# RS9110-N-11-22_Breakout.net
KiCad netlist of a schematic drawn in EAGLE
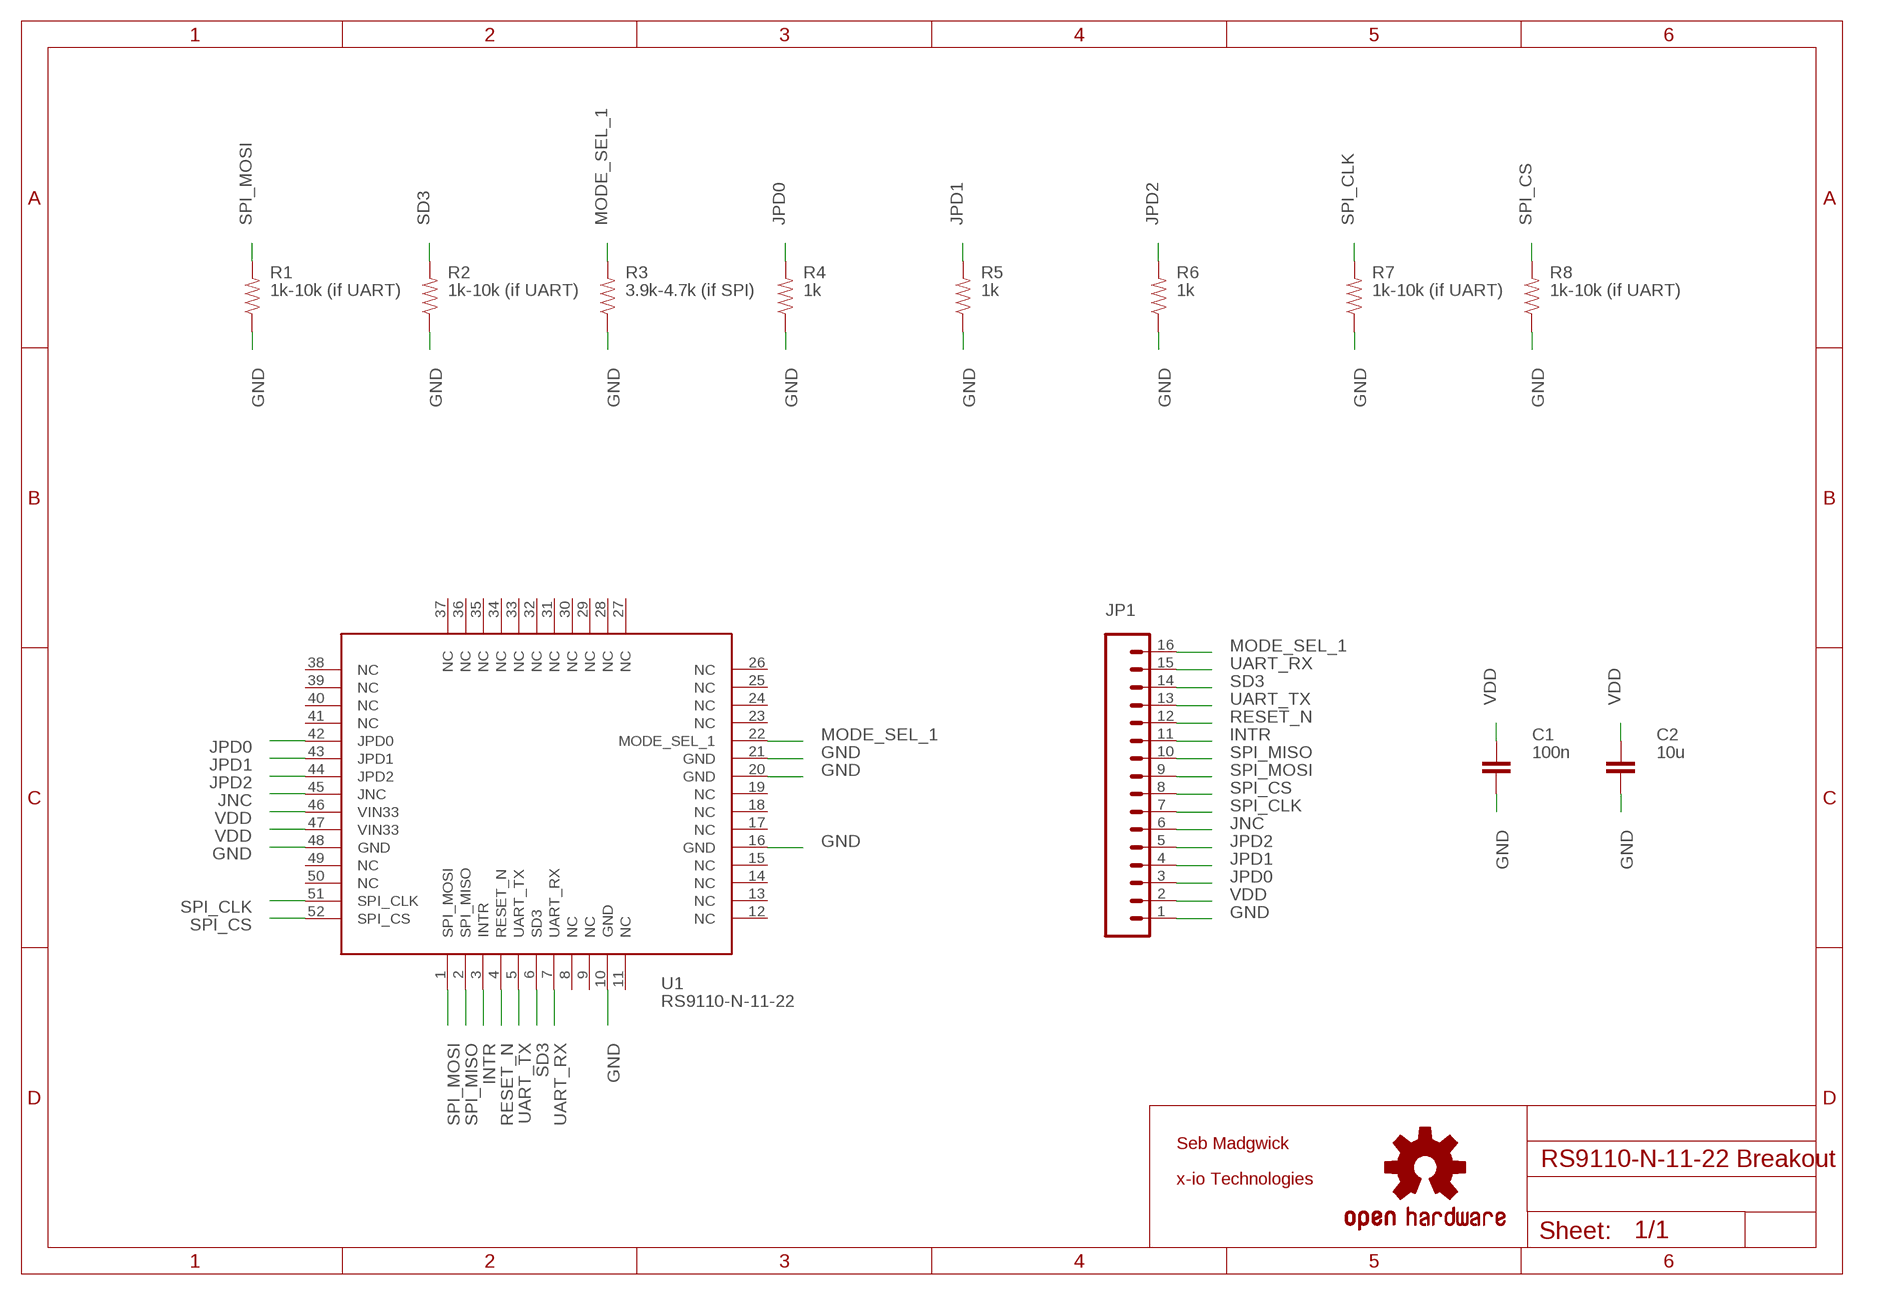
[diagram p0: schematic, sheet 1]

(export (version "E")
  (design (tool "Eeschema 10.0.6"))
  (components
    (comp (ref "C1")
      (value "100n")
      (footprint "eagle-import:0603-CAP")
      (libsource (lib "eagle-import") (part "CAP0603-CAP"))
    )
    (comp (ref "C2")
      (value "10u")
      (footprint "eagle-import:0603-CAP")
      (libsource (lib "eagle-import") (part "CAP0603-CAP"))
    )
    (comp (ref "JP1")
      (value "M16PTH")
      (footprint "eagle-import:1X16")
      (libsource (lib "eagle-import") (part "M16PTH"))
    )
    (comp (ref "LOGO1")
      (value "OSHW-LOGOS")
      (footprint "eagle-import:OSHW-LOGO-S")
      (libsource (lib "eagle-import") (part "OSHW-LOGOS"))
    )
    (comp (ref "R1")
      (value "1k-10k (if UART)")
      (footprint "eagle-import:0603-RES")
      (libsource (lib "eagle-import") (part "RESISTOR0603"))
    )
    (comp (ref "R2")
      (value "1k-10k (if UART)")
      (footprint "eagle-import:0603-RES")
      (libsource (lib "eagle-import") (part "RESISTOR0603"))
    )
    (comp (ref "R3")
      (value "3.9k-4.7k (if SPI)")
      (footprint "eagle-import:0603-RES")
      (libsource (lib "eagle-import") (part "RESISTOR0603"))
    )
    (comp (ref "R4")
      (value "1k")
      (footprint "eagle-import:0603-RES")
      (libsource (lib "eagle-import") (part "RESISTOR0603"))
    )
    (comp (ref "R5")
      (value "1k")
      (footprint "eagle-import:0603-RES")
      (libsource (lib "eagle-import") (part "RESISTOR0603"))
    )
    (comp (ref "R6")
      (value "1k")
      (footprint "eagle-import:0603-RES")
      (libsource (lib "eagle-import") (part "RESISTOR0603"))
    )
    (comp (ref "R7")
      (value "1k-10k (if UART)")
      (footprint "eagle-import:0603-RES")
      (libsource (lib "eagle-import") (part "RESISTOR0603"))
    )
    (comp (ref "R8")
      (value "1k-10k (if UART)")
      (footprint "eagle-import:0603-RES")
      (libsource (lib "eagle-import") (part "RESISTOR0603"))
    )
    (comp (ref "U1")
      (value "RS9110-N-11-22")
      (footprint "eagle-import:RS9110-N-11-22")
      (libsource (lib "eagle-import") (part "RS9110-N-11-22"))
    )
  )
  (nets
    (net (code "1") (name "/GND") (class "Default")
      (node (ref "C1") (pin "2") (pinfunction "2_2") (pintype "passive"))
      (node (ref "C2") (pin "2") (pinfunction "2_2") (pintype "passive"))
      (node (ref "JP1") (pin "1") (pinfunction "1_1") (pintype "passive"))
      (node (ref "R1") (pin "1") (pinfunction "1_1") (pintype "passive"))
      (node (ref "R2") (pin "1") (pinfunction "1_1") (pintype "passive"))
      (node (ref "R3") (pin "1") (pinfunction "1_1") (pintype "passive"))
      (node (ref "R4") (pin "1") (pinfunction "1_1") (pintype "passive"))
      (node (ref "R5") (pin "1") (pinfunction "1_1") (pintype "passive"))
      (node (ref "R6") (pin "1") (pinfunction "1_1") (pintype "passive"))
      (node (ref "R7") (pin "1") (pinfunction "1_1") (pintype "passive"))
      (node (ref "R8") (pin "1") (pinfunction "1_1") (pintype "passive"))
      (node (ref "U1") (pin "10") (pinfunction "GND_10") (pintype "bidirectional"))
      (node (ref "U1") (pin "16") (pinfunction "GND_16") (pintype "bidirectional"))
      (node (ref "U1") (pin "20") (pinfunction "GND_20") (pintype "bidirectional"))
      (node (ref "U1") (pin "21") (pinfunction "GND_21") (pintype "bidirectional"))
      (node (ref "U1") (pin "48") (pinfunction "GND_48") (pintype "bidirectional"))
    )
    (net (code "2") (name "/INTR") (class "Default")
      (node (ref "JP1") (pin "11") (pinfunction "11_11") (pintype "passive"))
      (node (ref "U1") (pin "3") (pinfunction "INTR_3") (pintype "bidirectional"))
    )
    (net (code "3") (name "/JNC") (class "Default")
      (node (ref "JP1") (pin "6") (pinfunction "6_6") (pintype "passive"))
      (node (ref "U1") (pin "45") (pinfunction "JNC_45") (pintype "bidirectional"))
    )
    (net (code "4") (name "/JPD0") (class "Default")
      (node (ref "JP1") (pin "3") (pinfunction "3_3") (pintype "passive"))
      (node (ref "R4") (pin "2") (pinfunction "2_2") (pintype "passive"))
      (node (ref "U1") (pin "42") (pinfunction "JPD0_42") (pintype "bidirectional"))
    )
    (net (code "5") (name "/JPD1") (class "Default")
      (node (ref "JP1") (pin "4") (pinfunction "4_4") (pintype "passive"))
      (node (ref "R5") (pin "2") (pinfunction "2_2") (pintype "passive"))
      (node (ref "U1") (pin "43") (pinfunction "JPD1_43") (pintype "bidirectional"))
    )
    (net (code "6") (name "/JPD2") (class "Default")
      (node (ref "JP1") (pin "5") (pinfunction "5_5") (pintype "passive"))
      (node (ref "R6") (pin "2") (pinfunction "2_2") (pintype "passive"))
      (node (ref "U1") (pin "44") (pinfunction "JPD2_44") (pintype "bidirectional"))
    )
    (net (code "7") (name "/MODE_SEL_1") (class "Default")
      (node (ref "JP1") (pin "16") (pinfunction "16_16") (pintype "passive"))
      (node (ref "R3") (pin "2") (pinfunction "2_2") (pintype "passive"))
      (node (ref "U1") (pin "22") (pinfunction "MODE_SEL_1_22") (pintype "bidirectional"))
    )
    (net (code "8") (name "/RESET_N") (class "Default")
      (node (ref "JP1") (pin "12") (pinfunction "12_12") (pintype "passive"))
      (node (ref "U1") (pin "4") (pinfunction "RESET_N_4") (pintype "bidirectional"))
    )
    (net (code "9") (name "/SD3") (class "Default")
      (node (ref "JP1") (pin "14") (pinfunction "14_14") (pintype "passive"))
      (node (ref "R2") (pin "2") (pinfunction "2_2") (pintype "passive"))
      (node (ref "U1") (pin "6") (pinfunction "SD3_6") (pintype "bidirectional"))
    )
    (net (code "10") (name "/SPI_CLK") (class "Default")
      (node (ref "JP1") (pin "7") (pinfunction "7_7") (pintype "passive"))
      (node (ref "R7") (pin "2") (pinfunction "2_2") (pintype "passive"))
      (node (ref "U1") (pin "51") (pinfunction "SPI_CLK_51") (pintype "bidirectional"))
    )
    (net (code "11") (name "/SPI_CS") (class "Default")
      (node (ref "JP1") (pin "8") (pinfunction "8_8") (pintype "passive"))
      (node (ref "R8") (pin "2") (pinfunction "2_2") (pintype "passive"))
      (node (ref "U1") (pin "52") (pinfunction "SPI_CS_52") (pintype "bidirectional"))
    )
    (net (code "12") (name "/SPI_MISO") (class "Default")
      (node (ref "JP1") (pin "10") (pinfunction "10_10") (pintype "passive"))
      (node (ref "U1") (pin "2") (pinfunction "SPI_MISO_2") (pintype "bidirectional"))
    )
    (net (code "13") (name "/SPI_MOSI") (class "Default")
      (node (ref "JP1") (pin "9") (pinfunction "9_9") (pintype "passive"))
      (node (ref "R1") (pin "2") (pinfunction "2_2") (pintype "passive"))
      (node (ref "U1") (pin "1") (pinfunction "SPI_MOSI_1") (pintype "bidirectional"))
    )
    (net (code "14") (name "/UART_RX") (class "Default")
      (node (ref "JP1") (pin "15") (pinfunction "15_15") (pintype "passive"))
      (node (ref "U1") (pin "7") (pinfunction "UART_RX_7") (pintype "bidirectional"))
    )
    (net (code "15") (name "/UART_TX") (class "Default")
      (node (ref "JP1") (pin "13") (pinfunction "13_13") (pintype "passive"))
      (node (ref "U1") (pin "5") (pinfunction "UART_TX_5") (pintype "bidirectional"))
    )
    (net (code "16") (name "/VDD") (class "Default")
      (node (ref "C1") (pin "1") (pinfunction "1_1") (pintype "passive"))
      (node (ref "C2") (pin "1") (pinfunction "1_1") (pintype "passive"))
      (node (ref "JP1") (pin "2") (pinfunction "2_2") (pintype "passive"))
      (node (ref "U1") (pin "46") (pinfunction "VIN33_46") (pintype "bidirectional"))
      (node (ref "U1") (pin "47") (pinfunction "VIN33_47") (pintype "bidirectional"))
    )
    (net (code "17") (name "unconnected-(U1-NC-Pad8)") (class "Default")
      (node (ref "U1") (pin "8") (pinfunction "NC_8") (pintype "bidirectional"))
    )
    (net (code "18") (name "unconnected-(U1-NC-Pad9)") (class "Default")
      (node (ref "U1") (pin "9") (pinfunction "NC_9") (pintype "bidirectional"))
    )
    (net (code "19") (name "unconnected-(U1-NC-Pad11)") (class "Default")
      (node (ref "U1") (pin "11") (pinfunction "NC_11") (pintype "bidirectional"))
    )
    (net (code "20") (name "unconnected-(U1-NC-Pad12)") (class "Default")
      (node (ref "U1") (pin "12") (pinfunction "NC_12") (pintype "bidirectional"))
    )
    (net (code "21") (name "unconnected-(U1-NC-Pad13)") (class "Default")
      (node (ref "U1") (pin "13") (pinfunction "NC_13") (pintype "bidirectional"))
    )
    (net (code "22") (name "unconnected-(U1-NC-Pad14)") (class "Default")
      (node (ref "U1") (pin "14") (pinfunction "NC_14") (pintype "bidirectional"))
    )
    (net (code "23") (name "unconnected-(U1-NC-Pad15)") (class "Default")
      (node (ref "U1") (pin "15") (pinfunction "NC_15") (pintype "bidirectional"))
    )
    (net (code "24") (name "unconnected-(U1-NC-Pad17)") (class "Default")
      (node (ref "U1") (pin "17") (pinfunction "NC_17") (pintype "bidirectional"))
    )
    (net (code "25") (name "unconnected-(U1-NC-Pad18)") (class "Default")
      (node (ref "U1") (pin "18") (pinfunction "NC_18") (pintype "bidirectional"))
    )
    (net (code "26") (name "unconnected-(U1-NC-Pad19)") (class "Default")
      (node (ref "U1") (pin "19") (pinfunction "NC_19") (pintype "bidirectional"))
    )
    (net (code "27") (name "unconnected-(U1-NC-Pad23)") (class "Default")
      (node (ref "U1") (pin "23") (pinfunction "NC_23") (pintype "bidirectional"))
    )
    (net (code "28") (name "unconnected-(U1-NC-Pad24)") (class "Default")
      (node (ref "U1") (pin "24") (pinfunction "NC_24") (pintype "bidirectional"))
    )
    (net (code "29") (name "unconnected-(U1-NC-Pad25)") (class "Default")
      (node (ref "U1") (pin "25") (pinfunction "NC_25") (pintype "bidirectional"))
    )
    (net (code "30") (name "unconnected-(U1-NC-Pad26)") (class "Default")
      (node (ref "U1") (pin "26") (pinfunction "NC_26") (pintype "bidirectional"))
    )
    (net (code "31") (name "unconnected-(U1-NC-Pad27)") (class "Default")
      (node (ref "U1") (pin "27") (pinfunction "NC_27") (pintype "bidirectional"))
    )
    (net (code "32") (name "unconnected-(U1-NC-Pad28)") (class "Default")
      (node (ref "U1") (pin "28") (pinfunction "NC_28") (pintype "bidirectional"))
    )
    (net (code "33") (name "unconnected-(U1-NC-Pad29)") (class "Default")
      (node (ref "U1") (pin "29") (pinfunction "NC_29") (pintype "bidirectional"))
    )
    (net (code "34") (name "unconnected-(U1-NC-Pad30)") (class "Default")
      (node (ref "U1") (pin "30") (pinfunction "NC_30") (pintype "bidirectional"))
    )
    (net (code "35") (name "unconnected-(U1-NC-Pad31)") (class "Default")
      (node (ref "U1") (pin "31") (pinfunction "NC_31") (pintype "bidirectional"))
    )
    (net (code "36") (name "unconnected-(U1-NC-Pad32)") (class "Default")
      (node (ref "U1") (pin "32") (pinfunction "NC_32") (pintype "bidirectional"))
    )
    (net (code "37") (name "unconnected-(U1-NC-Pad33)") (class "Default")
      (node (ref "U1") (pin "33") (pinfunction "NC_33") (pintype "bidirectional"))
    )
    (net (code "38") (name "unconnected-(U1-NC-Pad34)") (class "Default")
      (node (ref "U1") (pin "34") (pinfunction "NC_34") (pintype "bidirectional"))
    )
    (net (code "39") (name "unconnected-(U1-NC-Pad35)") (class "Default")
      (node (ref "U1") (pin "35") (pinfunction "NC_35") (pintype "bidirectional"))
    )
    (net (code "40") (name "unconnected-(U1-NC-Pad36)") (class "Default")
      (node (ref "U1") (pin "36") (pinfunction "NC_36") (pintype "bidirectional"))
    )
    (net (code "41") (name "unconnected-(U1-NC-Pad37)") (class "Default")
      (node (ref "U1") (pin "37") (pinfunction "NC_37") (pintype "bidirectional"))
    )
    (net (code "42") (name "unconnected-(U1-NC-Pad38)") (class "Default")
      (node (ref "U1") (pin "38") (pinfunction "NC_38") (pintype "bidirectional"))
    )
    (net (code "43") (name "unconnected-(U1-NC-Pad39)") (class "Default")
      (node (ref "U1") (pin "39") (pinfunction "NC_39") (pintype "bidirectional"))
    )
    (net (code "44") (name "unconnected-(U1-NC-Pad40)") (class "Default")
      (node (ref "U1") (pin "40") (pinfunction "NC_40") (pintype "bidirectional"))
    )
    (net (code "45") (name "unconnected-(U1-NC-Pad41)") (class "Default")
      (node (ref "U1") (pin "41") (pinfunction "NC_41") (pintype "bidirectional"))
    )
    (net (code "46") (name "unconnected-(U1-NC-Pad49)") (class "Default")
      (node (ref "U1") (pin "49") (pinfunction "NC_49") (pintype "bidirectional"))
    )
    (net (code "47") (name "unconnected-(U1-NC-Pad50)") (class "Default")
      (node (ref "U1") (pin "50") (pinfunction "NC_50") (pintype "bidirectional"))
    )
  )
)
